# main.net
KiCad netlist of a schematic drawn in Altium Designer
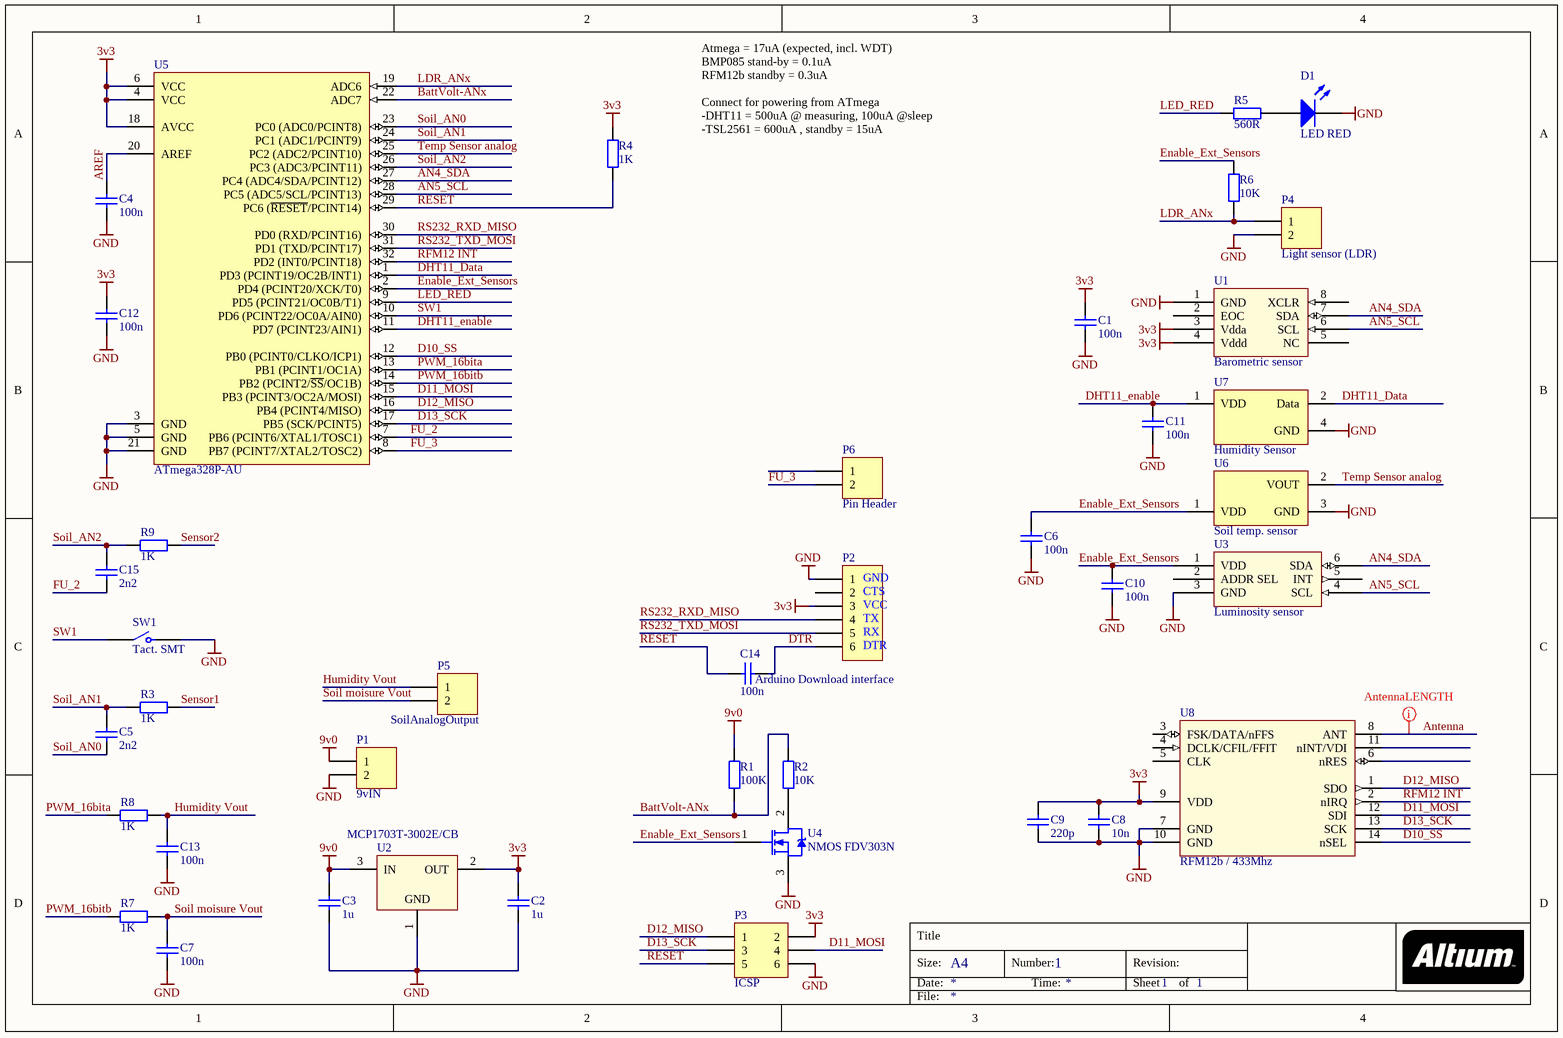
[diagram p0: main.SchDoc]

(export (version "E")
  (design (tool "Eeschema 10.0.6"))
  (components
    (comp (ref "C1") (value "100n") (footprint "C0805") (libsource (lib "OurDb") (part "cap_NonPolar")))
    (comp (ref "C2") (value "1u") (footprint "C0805") (libsource (lib "OurDb") (part "cap_NonPolar")))
    (comp (ref "C3") (value "1u") (footprint "C0805") (libsource (lib "OurDb") (part "cap_NonPolar")))
    (comp (ref "C4") (value "100n") (footprint "C0805") (libsource (lib "OurDb") (part "cap_NonPolar")))
    (comp (ref "C5") (value "2n2") (footprint "C0805") (libsource (lib "OurDb") (part "cap_NonPolar")))
    (comp (ref "C6") (value "100n") (footprint "C0805") (libsource (lib "OurDb") (part "cap_NonPolar")))
    (comp (ref "C7") (value "100n") (footprint "C0805") (libsource (lib "OurDb") (part "cap_NonPolar")))
    (comp (ref "C8") (value "10n") (footprint "C0805") (libsource (lib "OurDb") (part "cap_NonPolar")))
    (comp (ref "C9") (value "220p") (footprint "C0805") (libsource (lib "OurDb") (part "cap_NonPolar")))
    (comp (ref "C10") (value "100n") (footprint "C0805") (libsource (lib "OurDb") (part "cap_NonPolar")))
    (comp (ref "C11") (value "100n") (footprint "C0805") (libsource (lib "OurDb") (part "cap_NonPolar")))
    (comp (ref "C12") (value "100n") (footprint "C0805") (libsource (lib "OurDb") (part "cap_NonPolar")))
    (comp (ref "C13") (value "100n") (footprint "C0805") (libsource (lib "OurDb") (part "cap_NonPolar")))
    (comp (ref "C14") (value "100n") (footprint "C0805") (libsource (lib "OurDb") (part "cap_NonPolar")))
    (comp (ref "C15") (value "2n2") (footprint "C0805") (libsource (lib "OurDb") (part "cap_NonPolar")))
    (comp (ref "D1")
      (value "LED RED")
      (footprint "LED-3mm")
      (description "LED, Surface Mount LED Indicator")
      (fields (field (name "PART NUMBER") "Red-3mm"))
      (libsource (lib "OurDb") (part "LED_SINGLE"))
    )
    (comp (ref "P1")
      (value "9vIN")
      (footprint "PH1x2_2.54")
      (description "Con1x2")
      (fields (field (name "PART NUMBER") "PH1x2"))
      (libsource (lib "OurDb") (part "Con1x2"))
    )
    (comp (ref "P2")
      (value "Arduino Download interface")
      (footprint "PH1x6_2.54")
      (description "Con1x6")
      (fields (field (name "PART NUMBER") "PH1x6"))
      (libsource (lib "OurDb") (part "Con1x6"))
    )
    (comp (ref "P3")
      (value "ICSP")
      (footprint "PH2x3_2.54")
      (description "Header, 3-Pin, Dual row")
      (fields (field (name "PART NUMBER") "PH2x3"))
      (libsource (lib "OurDb") (part "Con2x3"))
    )
    (comp (ref "P4")
      (value "Light sensor (LDR)")
      (footprint "PH1x2_2.54")
      (description "Con1x2")
      (fields (field (name "PART NUMBER") "PH1x2"))
      (libsource (lib "OurDb") (part "Con1x2"))
    )
    (comp (ref "P5")
      (value "SoilAnalogOutput")
      (footprint "PH1x2_2.54")
      (description "Con1x2")
      (fields (field (name "PART NUMBER") "PH1x2"))
      (libsource (lib "OurDb") (part "Con1x2"))
    )
    (comp (ref "P6")
      (value "Pin Header")
      (footprint "PH1x2_2.54")
      (description "Con1x2")
      (fields (field (name "PART NUMBER") "PH1x2") (field (name "AUTHOR") "Willy Pietersz"))
      (libsource (lib "OurDb") (part "Con1x2"))
    )
    (comp (ref "R1")
      (value "RESISTOR")
      (footprint "R0805")
      (description "Resistor")
      (fields (field (name "PART NUMBER") "100K") (field (name "PUBLISHER") "Altium Limited"))
      (libsource (lib "OurDb") (part "RESISTOR"))
    )
    (comp (ref "R2")
      (value "RESISTOR")
      (footprint "R0805")
      (description "Resistor")
      (fields (field (name "PART NUMBER") "10K") (field (name "PUBLISHER") "Altium Limited"))
      (libsource (lib "") (part "RESISTOR_1"))
    )
    (comp (ref "R3")
      (value "RESISTOR")
      (footprint "R0805")
      (description "Resistor")
      (fields (field (name "PART NUMBER") "1K") (field (name "PUBLISHER") "Altium Limited"))
      (libsource (lib "") (part "RESISTOR_2"))
    )
    (comp (ref "R4")
      (value "RESISTOR")
      (footprint "R0805")
      (description "Resistor")
      (fields (field (name "PART NUMBER") "1K") (field (name "PUBLISHER") "Altium Limited"))
      (libsource (lib "OurDb") (part "RESISTOR"))
    )
    (comp (ref "R5")
      (value "RESISTOR")
      (footprint "R0805")
      (description "Resistor")
      (fields (field (name "PART NUMBER") "560R") (field (name "PUBLISHER") "Altium Limited"))
      (libsource (lib "") (part "RESISTOR_3"))
    )
    (comp (ref "R6")
      (value "RESISTOR")
      (footprint "R0805")
      (description "Resistor")
      (fields (field (name "PART NUMBER") "10K") (field (name "PUBLISHER") "Altium Limited"))
      (libsource (lib "OurDb") (part "RESISTOR"))
    )
    (comp (ref "R7")
      (value "RESISTOR")
      (footprint "R0805")
      (description "Resistor")
      (fields (field (name "PART NUMBER") "1K") (field (name "PUBLISHER") "Altium Limited"))
      (libsource (lib "") (part "RESISTOR_2"))
    )
    (comp (ref "R8")
      (value "RESISTOR")
      (footprint "R0805")
      (description "Resistor")
      (fields (field (name "PART NUMBER") "1K") (field (name "PUBLISHER") "Altium Limited"))
      (libsource (lib "") (part "RESISTOR_2"))
    )
    (comp (ref "R9")
      (value "RESISTOR")
      (footprint "R0805")
      (description "Resistor")
      (fields (field (name "PART NUMBER") "1K") (field (name "PUBLISHER") "Altium Limited"))
      (libsource (lib "") (part "RESISTOR_2"))
    )
    (comp (ref "SW1")
      (value "Tact. SMT")
      (footprint "Switch TACT 3.5*6")
      (description "Switch")
      (fields
        (field (name "PART NUMBER") "Pushbutton TACT mini 3.5x6")
        (field (name "VOLTAGE") "42")
        (field (name "AUTHOR") "Willem Pietersz")
      )
      (libsource (lib "OurDb") (part "SW-TACT 2p"))
    )
    (comp (ref "U1")
      (value "Barometric sensor")
      (footprint "BMP085")
      (description "Sensor, Barometric")
      (fields (field (name "PART NUMBER") "BMP085"))
      (libsource (lib "OurDb") (part "BMP085"))
    )
    (comp (ref "U2")
      (value "MCP1703T")
      (footprint "SOT23")
      (description "Regulator, 5v")
      (fields (field (name "PART NUMBER") "MCP1703T-3002E/CB"))
      (libsource (lib "OurDb") (part "AMS1117"))
    )
    (comp (ref "U3")
      (value "Luminosity sensor")
      (footprint "TSL2561")
      (description "Sensor, Illumination")
      (fields (field (name "PART NUMBER") "TSL2561"))
      (libsource (lib "OurDb") (part "TSL2561"))
    )
    (comp (ref "U4")
      (value "NMOS FDV303N")
      (footprint "SOT-23-FET")
      (description "Transistor")
      (fields (field (name "PART NUMBER") "FDV303N"))
      (libsource (lib "OurDb") (part "NMOS"))
    )
    (comp (ref "U5")
      (value "ATmega328P-AU")
      (footprint "atmel_32A_N")
      (fields (field (name "PUBLISHER") "Altium Limited"))
      (libsource (lib "AltiumDatabaseSelection") (part "ATmega328P-AU"))
    )
    (comp (ref "U6")
      (value "Soil temp. sensor")
      (footprint "SOT-23-TT3_M")
      (description "Low-Power Linear Active Thermistor IC, 3-Pin SOT-23, Extended Temperature, Tape and Reel")
      (fields (field (name "PART NUMBER") "MCP9700AT-E/TT"))
      (libsource (lib "OurDb") (part "MCP9700AT-E/TT"))
    )
    (comp (ref "U7")
      (value "Humidity Sensor")
      (footprint "DHTXX")
      (description "Humidity / Temp Sensor")
      (fields (field (name "PART NUMBER") "DHT11"))
      (libsource (lib "OurDb") (part "DHT11"))
    )
    (comp (ref "U8")
      (value "RFM12b / 433Mhz")
      (footprint "RFM12_dev")
      (description "Wireless, Transceiver")
      (fields (field (name "PART NUMBER") "RFM12b"))
      (libsource (lib "OurDb") (part "RFM12B"))
    )
  )
  (nets
    (net (code "1") (name "/AN4_SDA") (class "Default")
      (node (ref "U1") (pin "7") (pinfunction "SDA_7") (pintype "bidirectional"))
      (node (ref "U3") (pin "6") (pinfunction "SDA_6") (pintype "bidirectional"))
      (node (ref "U5") (pin "27") (pinfunction "PC4_(ADC4/SDA/PCINT12)_27") (pintype "bidirectional"))
    )
    (net (code "2") (name "/AN5_SCL") (class "Default")
      (node (ref "U1") (pin "6") (pinfunction "SCL_6") (pintype "input"))
      (node (ref "U3") (pin "4") (pinfunction "SCL_4") (pintype "input"))
      (node (ref "U5") (pin "28") (pinfunction "PC5_(ADC5/SCL/PCINT13)_28") (pintype "bidirectional"))
    )
    (net (code "3") (name "/AREF") (class "Default")
      (node (ref "C4") (pin "2") (pinfunction "2_2") (pintype "passive"))
      (node (ref "U5") (pin "20") (pinfunction "AREF_20") (pintype "passive"))
    )
    (net (code "4") (name "/Antenna") (class "Default")
      (node (ref "U8") (pin "8") (pinfunction "ANT_8") (pintype "power_in"))
    )
    (net (code "5") (name "/BattVolt-ANx") (class "Default")
      (node (ref "R1") (pin "2") (pinfunction "2_2") (pintype "passive"))
      (node (ref "R2") (pin "2") (pinfunction "2_2") (pintype "passive"))
      (node (ref "U5") (pin "22") (pinfunction "ADC7_22") (pintype "input"))
    )
    (net (code "6") (name "/D10_SS") (class "Default")
      (node (ref "U5") (pin "12") (pinfunction "PB0_(PCINT0/CLKO/ICP1)_12") (pintype "bidirectional"))
      (node (ref "U8") (pin "14") (pinfunction "nSEL_14") (pintype "passive"))
    )
    (net (code "7") (name "/D11_MOSI") (class "Default")
      (node (ref "P3") (pin "4") (pinfunction "4_4") (pintype "passive"))
      (node (ref "U5") (pin "15") (pinfunction "PB3_(PCINT3/OC2A/MOSI)_15") (pintype "bidirectional"))
      (node (ref "U8") (pin "12") (pinfunction "SDI_12") (pintype "passive"))
    )
    (net (code "8") (name "/D12_MISO") (class "Default")
      (node (ref "P3") (pin "1") (pinfunction "1_1") (pintype "passive"))
      (node (ref "U5") (pin "16") (pinfunction "PB4_(PCINT4/MISO)_16") (pintype "bidirectional"))
      (node (ref "U8") (pin "1") (pinfunction "SDO_1") (pintype "output"))
    )
    (net (code "9") (name "/D13_SCK") (class "Default")
      (node (ref "P3") (pin "3") (pinfunction "3_3") (pintype "passive"))
      (node (ref "U5") (pin "17") (pinfunction "PB5_(SCK/PCINT5)_17") (pintype "bidirectional"))
      (node (ref "U8") (pin "13") (pinfunction "SCK_13") (pintype "passive"))
    )
    (net (code "10") (name "/DHT11_Data") (class "Default")
      (node (ref "U5") (pin "1") (pinfunction "PD3_(PCINT19/OC2B/INT1)_1") (pintype "bidirectional"))
      (node (ref "U7") (pin "2") (pinfunction "Data_2") (pintype "power_in"))
    )
    (net (code "11") (name "/DHT11_enable") (class "Default")
      (node (ref "C11") (pin "2") (pinfunction "2_2") (pintype "passive"))
      (node (ref "U5") (pin "11") (pinfunction "PD7_(PCINT23/AIN1)_11") (pintype "bidirectional"))
      (node (ref "U7") (pin "1") (pinfunction "VDD_1") (pintype "power_in"))
    )
    (net (code "12") (name "/DTR") (class "Default")
      (node (ref "C14") (pin "2") (pinfunction "2_2") (pintype "passive"))
      (node (ref "P2") (pin "6") (pinfunction "6_6") (pintype "passive"))
    )
    (net (code "13") (name "/Enable_Ext_Sensors") (class "Default")
      (node (ref "C10") (pin "2") (pinfunction "2_2") (pintype "passive"))
      (node (ref "C6") (pin "2") (pinfunction "2_2") (pintype "passive"))
      (node (ref "R6") (pin "1") (pinfunction "1_1") (pintype "passive"))
      (node (ref "U3") (pin "1") (pinfunction "VDD_1") (pintype "power_in"))
      (node (ref "U4") (pin "1") (pinfunction "G_1") (pintype "passive"))
      (node (ref "U5") (pin "2") (pinfunction "PD4_(PCINT20/XCK/T0)_2") (pintype "bidirectional"))
      (node (ref "U6") (pin "1") (pinfunction "VDD_1") (pintype "power_in"))
    )
    (net (code "14") (name "/FU_2") (class "Default")
      (node (ref "C15") (pin "1") (pinfunction "1_1") (pintype "passive"))
      (node (ref "U5") (pin "7") (pinfunction "PB6_(PCINT6/XTAL1/TOSC1)_7") (pintype "bidirectional"))
    )
    (net (code "15") (name "/FU_3") (class "Default")
      (node (ref "P6") (pin "2") (pinfunction "2_2") (pintype "passive"))
      (node (ref "U5") (pin "8") (pinfunction "PB7_(PCINT7/XTAL2/TOSC2)_8") (pintype "bidirectional"))
    )
    (net (code "16") (name "/Humidity Vout") (class "Default")
      (node (ref "C13") (pin "2") (pinfunction "2_2") (pintype "passive"))
      (node (ref "P5") (pin "1") (pinfunction "1_1") (pintype "passive"))
      (node (ref "R8") (pin "1") (pinfunction "1_1") (pintype "passive"))
    )
    (net (code "17") (name "/LDR_ANx") (class "Default")
      (node (ref "P4") (pin "1") (pinfunction "1_1") (pintype "passive"))
      (node (ref "R6") (pin "2") (pinfunction "2_2") (pintype "passive"))
      (node (ref "U5") (pin "19") (pinfunction "ADC6_19") (pintype "input"))
    )
    (net (code "18") (name "/LED_RED") (class "Default")
      (node (ref "R5") (pin "1") (pinfunction "1_1") (pintype "passive"))
      (node (ref "U5") (pin "9") (pinfunction "PD5_(PCINT21/OC0B/T1)_9") (pintype "bidirectional"))
    )
    (net (code "19") (name "/PWM_16bita") (class "Default")
      (node (ref "R8") (pin "2") (pinfunction "2_2") (pintype "passive"))
      (node (ref "U5") (pin "13") (pinfunction "PB1_(PCINT1/OC1A)_13") (pintype "bidirectional"))
    )
    (net (code "20") (name "/PWM_16bitb") (class "Default")
      (node (ref "R7") (pin "2") (pinfunction "2_2") (pintype "passive"))
      (node (ref "U5") (pin "14") (pinfunction "PB2_(PCINT2/~{SS}/OC1B)_14") (pintype "bidirectional"))
    )
    (net (code "21") (name "/RESET") (class "Default")
      (node (ref "C14") (pin "1") (pinfunction "1_1") (pintype "passive"))
      (node (ref "P3") (pin "5") (pinfunction "5_5") (pintype "passive"))
      (node (ref "R4") (pin "2") (pinfunction "2_2") (pintype "passive"))
      (node (ref "U5") (pin "29") (pinfunction "PC6_(~{RESET}/PCINT14)_29") (pintype "bidirectional"))
    )
    (net (code "22") (name "/RFM12 INT") (class "Default")
      (node (ref "U5") (pin "32") (pinfunction "PD2_(INT0/PCINT18)_32") (pintype "bidirectional"))
      (node (ref "U8") (pin "2") (pinfunction "nIRQ_2") (pintype "output"))
    )
    (net (code "23") (name "/RS232_RXD_MISO") (class "Default")
      (node (ref "P2") (pin "4") (pinfunction "4_4") (pintype "passive"))
      (node (ref "U5") (pin "30") (pinfunction "PD0_(RXD/PCINT16)_30") (pintype "bidirectional"))
    )
    (net (code "24") (name "/RS232_TXD_MOSI") (class "Default")
      (node (ref "P2") (pin "5") (pinfunction "5_5") (pintype "passive"))
      (node (ref "U5") (pin "31") (pinfunction "PD1_(TXD/PCINT17)_31") (pintype "bidirectional"))
    )
    (net (code "25") (name "/SW1") (class "Default")
      (node (ref "SW1") (pin "1") (pintype "passive"))
      (node (ref "U5") (pin "10") (pinfunction "PD6_(PCINT22/OC0A/AIN0)_10") (pintype "bidirectional"))
    )
    (net (code "26") (name "/Sensor1") (class "Default")
      (node (ref "R3") (pin "1") (pinfunction "1_1") (pintype "passive"))
    )
    (net (code "27") (name "/Sensor2") (class "Default")
      (node (ref "R9") (pin "1") (pinfunction "1_1") (pintype "passive"))
    )
    (net (code "28") (name "/Soil moisure Vout") (class "Default")
      (node (ref "C7") (pin "2") (pinfunction "2_2") (pintype "passive"))
      (node (ref "P5") (pin "2") (pinfunction "2_2") (pintype "passive"))
      (node (ref "R7") (pin "1") (pinfunction "1_1") (pintype "passive"))
    )
    (net (code "29") (name "/Soil_AN0") (class "Default")
      (node (ref "C5") (pin "1") (pinfunction "1_1") (pintype "passive"))
      (node (ref "U5") (pin "23") (pinfunction "PC0_(ADC0/PCINT8)_23") (pintype "bidirectional"))
    )
    (net (code "30") (name "/Soil_AN1") (class "Default")
      (node (ref "C5") (pin "2") (pinfunction "2_2") (pintype "passive"))
      (node (ref "R3") (pin "2") (pinfunction "2_2") (pintype "passive"))
      (node (ref "U5") (pin "24") (pinfunction "PC1_(ADC1/PCINT9)_24") (pintype "bidirectional"))
    )
    (net (code "31") (name "/Soil_AN2") (class "Default")
      (node (ref "C15") (pin "2") (pinfunction "2_2") (pintype "passive"))
      (node (ref "R9") (pin "2") (pinfunction "2_2") (pintype "passive"))
      (node (ref "U5") (pin "26") (pinfunction "PC3_(ADC3/PCINT11)_26") (pintype "bidirectional"))
    )
    (net (code "32") (name "/Temp Sensor analog") (class "Default")
      (node (ref "U5") (pin "25") (pinfunction "PC2_(ADC2/PCINT10)_25") (pintype "bidirectional"))
      (node (ref "U6") (pin "2") (pinfunction "VOUT_2") (pintype "power_in"))
    )
    (net (code "33") (name "3v3") (class "Default")
      (node (ref "C1") (pin "2") (pinfunction "2_2") (pintype "passive"))
      (node (ref "C12") (pin "2") (pinfunction "2_2") (pintype "passive"))
      (node (ref "C2") (pin "2") (pinfunction "2_2") (pintype "passive"))
      (node (ref "C8") (pin "2") (pinfunction "2_2") (pintype "passive"))
      (node (ref "C9") (pin "2") (pinfunction "2_2") (pintype "passive"))
      (node (ref "P2") (pin "3") (pinfunction "3_3") (pintype "passive"))
      (node (ref "P3") (pin "2") (pinfunction "2_2") (pintype "passive"))
      (node (ref "R4") (pin "1") (pinfunction "1_1") (pintype "passive"))
      (node (ref "U1") (pin "3") (pinfunction "Vdda_3") (pintype "power_in"))
      (node (ref "U1") (pin "4") (pinfunction "Vddd_4") (pintype "power_in"))
      (node (ref "U2") (pin "2") (pinfunction "OUT_2") (pintype "power_in"))
      (node (ref "U5") (pin "18") (pinfunction "AVCC_18") (pintype "power_in"))
      (node (ref "U5") (pin "4") (pinfunction "VCC_4") (pintype "power_in"))
      (node (ref "U5") (pin "6") (pinfunction "VCC_6") (pintype "power_in"))
      (node (ref "U8") (pin "9") (pinfunction "VDD_9") (pintype "power_in"))
    )
    (net (code "34") (name "9v0") (class "Default")
      (node (ref "C3") (pin "2") (pinfunction "2_2") (pintype "passive"))
      (node (ref "P1") (pin "1") (pinfunction "1_1") (pintype "passive"))
      (node (ref "R1") (pin "1") (pinfunction "1_1") (pintype "passive"))
      (node (ref "U2") (pin "3") (pinfunction "IN_3") (pintype "passive"))
    )
    (net (code "35") (name "GND") (class "Default")
      (node (ref "C1") (pin "1") (pinfunction "1_1") (pintype "passive"))
      (node (ref "C10") (pin "1") (pinfunction "1_1") (pintype "passive"))
      (node (ref "C11") (pin "1") (pinfunction "1_1") (pintype "passive"))
      (node (ref "C12") (pin "1") (pinfunction "1_1") (pintype "passive"))
      (node (ref "C13") (pin "1") (pinfunction "1_1") (pintype "passive"))
      (node (ref "C2") (pin "1") (pinfunction "1_1") (pintype "passive"))
      (node (ref "C3") (pin "1") (pinfunction "1_1") (pintype "passive"))
      (node (ref "C4") (pin "1") (pinfunction "1_1") (pintype "passive"))
      (node (ref "C6") (pin "1") (pinfunction "1_1") (pintype "passive"))
      (node (ref "C7") (pin "1") (pinfunction "1_1") (pintype "passive"))
      (node (ref "C8") (pin "1") (pinfunction "1_1") (pintype "passive"))
      (node (ref "C9") (pin "1") (pinfunction "1_1") (pintype "passive"))
      (node (ref "D1") (pin "2") (pinfunction "K_2") (pintype "passive"))
      (node (ref "P1") (pin "2") (pinfunction "2_2") (pintype "passive"))
      (node (ref "P2") (pin "1") (pinfunction "1_1") (pintype "passive"))
      (node (ref "P3") (pin "6") (pinfunction "6_6") (pintype "passive"))
      (node (ref "P4") (pin "2") (pinfunction "2_2") (pintype "passive"))
      (node (ref "SW1") (pin "2") (pintype "passive"))
      (node (ref "U1") (pin "1") (pinfunction "GND_1") (pintype "power_in"))
      (node (ref "U2") (pin "1") (pinfunction "GND_1") (pintype "passive"))
      (node (ref "U3") (pin "3") (pinfunction "GND_3") (pintype "power_in"))
      (node (ref "U4") (pin "3") (pinfunction "S_3") (pintype "passive"))
      (node (ref "U5") (pin "21") (pinfunction "GND_21") (pintype "power_in"))
      (node (ref "U5") (pin "3") (pinfunction "GND_3") (pintype "power_in"))
      (node (ref "U5") (pin "5") (pinfunction "GND_5") (pintype "power_in"))
      (node (ref "U6") (pin "3") (pinfunction "GND_3") (pintype "power_in"))
      (node (ref "U7") (pin "4") (pinfunction "GND_4") (pintype "power_in"))
      (node (ref "U8") (pin "10") (pinfunction "GND_10") (pintype "power_in"))
      (node (ref "U8") (pin "7") (pinfunction "GND_7") (pintype "power_in"))
    )
    (net (code "36") (name "Net-(D1-A)") (class "Default")
      (node (ref "D1") (pin "1") (pinfunction "A_1") (pintype "passive"))
      (node (ref "R5") (pin "2") (pinfunction "2_2") (pintype "passive"))
    )
    (net (code "37") (name "Net-(U4-D)") (class "Default")
      (node (ref "R2") (pin "1") (pinfunction "1_1") (pintype "passive"))
      (node (ref "U4") (pin "2") (pinfunction "D_2") (pintype "passive"))
    )
    (net (code "38") (name "unconnected-(P2-Pad2)") (class "Default")
      (node (ref "P2") (pin "2") (pinfunction "2_2") (pintype "passive"))
    )
    (net (code "39") (name "unconnected-(P6-Pad1)") (class "Default")
      (node (ref "P6") (pin "1") (pinfunction "1_1") (pintype "passive"))
    )
    (net (code "40") (name "unconnected-(U1-EOC-Pad2)") (class "Default")
      (node (ref "U1") (pin "2") (pinfunction "EOC_2") (pintype "passive"))
    )
    (net (code "41") (name "unconnected-(U1-NC-Pad5)") (class "Default")
      (node (ref "U1") (pin "5") (pinfunction "NC_5") (pintype "passive"))
    )
    (net (code "42") (name "unconnected-(U1-XCLR-Pad8)") (class "Default")
      (node (ref "U1") (pin "8") (pinfunction "XCLR_8") (pintype "input"))
    )
    (net (code "43") (name "unconnected-(U3-ADDR_SEL-Pad2)") (class "Default")
      (node (ref "U3") (pin "2") (pinfunction "ADDR_SEL_2") (pintype "passive"))
    )
    (net (code "44") (name "unconnected-(U3-INT-Pad5)") (class "Default")
      (node (ref "U3") (pin "5") (pinfunction "INT_5") (pintype "output"))
    )
    (net (code "45") (name "unconnected-(U8-CLK-Pad5)") (class "Default")
      (node (ref "U8") (pin "5") (pinfunction "CLK_5") (pintype "power_in"))
    )
    (net (code "46") (name "unconnected-(U8-DCLK{slash}CFIL{slash}FFIT-Pad4)") (class "Default")
      (node (ref "U8") (pin "4") (pinfunction "DCLK/CFIL/FFIT_4") (pintype "input"))
    )
    (net (code "47") (name "unconnected-(U8-FSK{slash}DATA{slash}nFFS-Pad3)") (class "Default")
      (node (ref "U8") (pin "3") (pinfunction "FSK/DATA/nFFS_3") (pintype "bidirectional"))
    )
    (net (code "48") (name "unconnected-(U8-nINT{slash}VDI-Pad11)") (class "Default")
      (node (ref "U8") (pin "11") (pinfunction "nINT/VDI_11") (pintype "passive"))
    )
    (net (code "49") (name "unconnected-(U8-nRES-Pad6)") (class "Default")
      (node (ref "U8") (pin "6") (pinfunction "nRES_6") (pintype "bidirectional"))
    )
  )
)
